# Power.net
KiCad netlist of a schematic drawn in Altium Designer
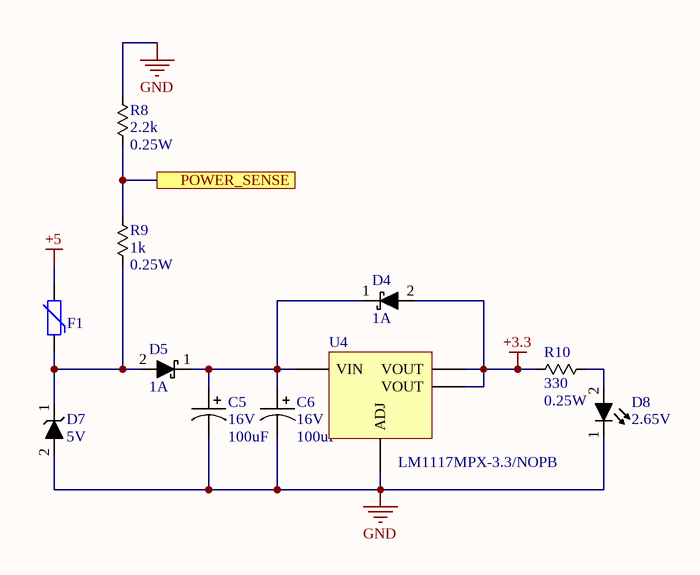
[diagram p0: Power.SchDoc]

(export (version "E")
  (design (tool "Eeschema 10.0.6"))
  (components
    (comp (ref "C5")
      (value "cap_single_p")
      (footprint "chip_2917_AVX_TAJD")
      (description "CAP, 100uF, ±10%, 16V, Tantalum, 2917")
      (fields
        (field (name "TOLERANCE") "±10%")
        (field (name "VOLTAGE RATING") "16V")
        (field (name "CAPACITANCE") "100uF")
        (field (name "PART NUMBER") "CAP-00550")
      )
      (libsource (lib "Capacitors") (part "cap_single_p"))
    )
    (comp (ref "C6")
      (value "cap_single_p")
      (footprint "chip_2917_AVX_TAJD")
      (description "CAP, 100uF, ±10%, 16V, Tantalum, 2917")
      (fields
        (field (name "TOLERANCE") "±10%")
        (field (name "VOLTAGE RATING") "16V")
        (field (name "CAPACITANCE") "100uF")
        (field (name "PART NUMBER") "CAP-00550")
      )
      (libsource (lib "Capacitors") (part "cap_single_p"))
    )
    (comp (ref "D4")
      (value "diode_2")
      (footprint "sod123_0")
      (description "Dio Shtky, 1A, 0.55V, 40V, SOD-123")
      (fields
        (field (name "CURRENT RATING") "1A")
        (field (name "PART NUMBER") "DIO-00001")
        (field (name "MANUFACTURER") "ON Semi")
      )
      (libsource (lib "Diodes") (part "diode_2"))
    )
    (comp (ref "D5")
      (value "diode_2")
      (footprint "sod123_0")
      (description "Dio Shtky, 1A, 0.55V, 40V, SOD-123")
      (fields
        (field (name "CURRENT RATING") "1A")
        (field (name "PART NUMBER") "DIO-00001")
        (field (name "MANUFACTURER") "ON Semi")
      )
      (libsource (lib "Diodes") (part "diode_2"))
    )
    (comp (ref "D7")
      (value "diode_1")
      (footprint "do-214ac")
      (description "TVS, 5V, 400W, Unidirectional")
      (fields
        (field (name "REVERSE BREAKDOWN VOLTAGE") "5V")
        (field (name "PART NUMBER") "DIO-00036")
        (field (name "MANUFACTURER") "ST")
      )
      (libsource (lib "Diodes") (part "diode_1"))
    )
    (comp (ref "D8")
      (value "diode_4")
      (footprint "chip_0603")
      (description "LED, Green, 0603, Low current, HELI2 Series")
      (fields
        (field (name "FORWARD VOLTAGE") "2.65V")
        (field (name "PART NUMBER") "DIO-00050")
        (field (name "MANUFACTURER") "Kingbright")
      )
      (libsource (lib "Diodes") (part "diode_4"))
    )
    (comp (ref "F1")
      (value "PTC_0")
      (footprint "chip_1206")
      (description "PTC Resettable fuse, 6V, 500mA, 1206")
      (fields (field (name "PART NUMBER") "MISC-00008") (field (name "MANUFACTURER") "Eaton"))
      (libsource (lib "Misc") (part "PTC_0"))
    )
    (comp (ref "R8")
      (value "res_single")
      (footprint "chip_0603")
      (description "RES SMD 2.2K OHM 1% 1/4W 0603")
      (fields
        (field (name "TOLERANCE") "1%")
        (field (name "RESISTANCE") "2.2k")
        (field (name "POWER RATING") "0.25W")
        (field (name "PART NUMBER") "RES-00365")
      )
      (libsource (lib "Resistors") (part "res_single"))
    )
    (comp (ref "R9")
      (value "res_single")
      (footprint "chip_0603")
      (description "RES SMD 1K OHM 1% 1/4W 0603")
      (fields
        (field (name "TOLERANCE") "1%")
        (field (name "RESISTANCE") "1k")
        (field (name "POWER RATING") "0.25W")
        (field (name "PART NUMBER") "RES-00360")
      )
      (libsource (lib "Resistors") (part "res_single"))
    )
    (comp (ref "R10")
      (value "res_single")
      (footprint "chip_0603")
      (description "RES SMD 330 OHM 1% 1/4W 0603")
      (fields
        (field (name "TOLERANCE") "1%")
        (field (name "RESISTANCE") "330")
        (field (name "POWER RATING") "0.25W")
        (field (name "PART NUMBER") "RES-00221")
      )
      (libsource (lib "Resistors") (part "res_single"))
    )
    (comp (ref "U4")
      (value "LM1117")
      (footprint "sot-223-4")
      (description "REG, Linear, Fixed 3V3, 800mA, SOT-223")
      (fields
        (field (name "MANUFACTURER PN") "LM1117MPX-3.3/NOPB")
        (field (name "PART NUMBER") "PWREG-00018")
        (field (name "MANUFACTURER") "TI")
      )
      (libsource (lib "Power Reg") (part "LM1117"))
    )
  )
  (nets
    (net (code "1") (name "+3.3") (class "Default")
      (node (ref "D4") (pin "2") (pinfunction "2_2") (pintype "passive"))
      (node (ref "R10") (pin "1") (pinfunction "1_1") (pintype "passive"))
      (node (ref "U4") (pin "2") (pinfunction "VOUT_2") (pintype "passive"))
      (node (ref "U4") (pin "4") (pinfunction "VOUT_4") (pintype "passive"))
    )
    (net (code "2") (name "+5") (class "Default")
      (node (ref "F1") (pin "2") (pinfunction "2_2") (pintype "passive"))
    )
    (net (code "3") (name "/POWER_SENSE") (class "Default")
      (node (ref "R8") (pin "2") (pinfunction "2_2") (pintype "passive"))
      (node (ref "R9") (pin "1") (pinfunction "1_1") (pintype "passive"))
    )
    (net (code "4") (name "GND") (class "Default")
      (node (ref "C5") (pin "2") (pinfunction "2_2") (pintype "passive"))
      (node (ref "C6") (pin "2") (pinfunction "2_2") (pintype "passive"))
      (node (ref "D7") (pin "2") (pinfunction "2_2") (pintype "passive"))
      (node (ref "D8") (pin "1") (pinfunction "1_1") (pintype "passive"))
      (node (ref "R8") (pin "1") (pinfunction "1_1") (pintype "passive"))
      (node (ref "U4") (pin "1") (pinfunction "ADJ_1") (pintype "passive"))
    )
    (net (code "5") (name "Net-(D5-Pad2)") (class "Default")
      (node (ref "D5") (pin "2") (pinfunction "2_2") (pintype "passive"))
      (node (ref "D7") (pin "1") (pinfunction "1_1") (pintype "passive"))
      (node (ref "F1") (pin "1") (pinfunction "1_1") (pintype "passive"))
      (node (ref "R9") (pin "2") (pinfunction "2_2") (pintype "passive"))
    )
    (net (code "6") (name "Net-(D8-Pad2)") (class "Default")
      (node (ref "D8") (pin "2") (pinfunction "2_2") (pintype "passive"))
      (node (ref "R10") (pin "2") (pinfunction "2_2") (pintype "passive"))
    )
    (net (code "7") (name "Net-(U4-VIN)") (class "Default")
      (node (ref "C5") (pin "1") (pinfunction "1_1") (pintype "passive"))
      (node (ref "C6") (pin "1") (pinfunction "1_1") (pintype "passive"))
      (node (ref "D4") (pin "1") (pinfunction "1_1") (pintype "passive"))
      (node (ref "D5") (pin "1") (pinfunction "1_1") (pintype "passive"))
      (node (ref "U4") (pin "3") (pinfunction "VIN_3") (pintype "passive"))
    )
  )
)
